# Power_MPU.net
KiCad netlist of a schematic drawn in Altium Designer
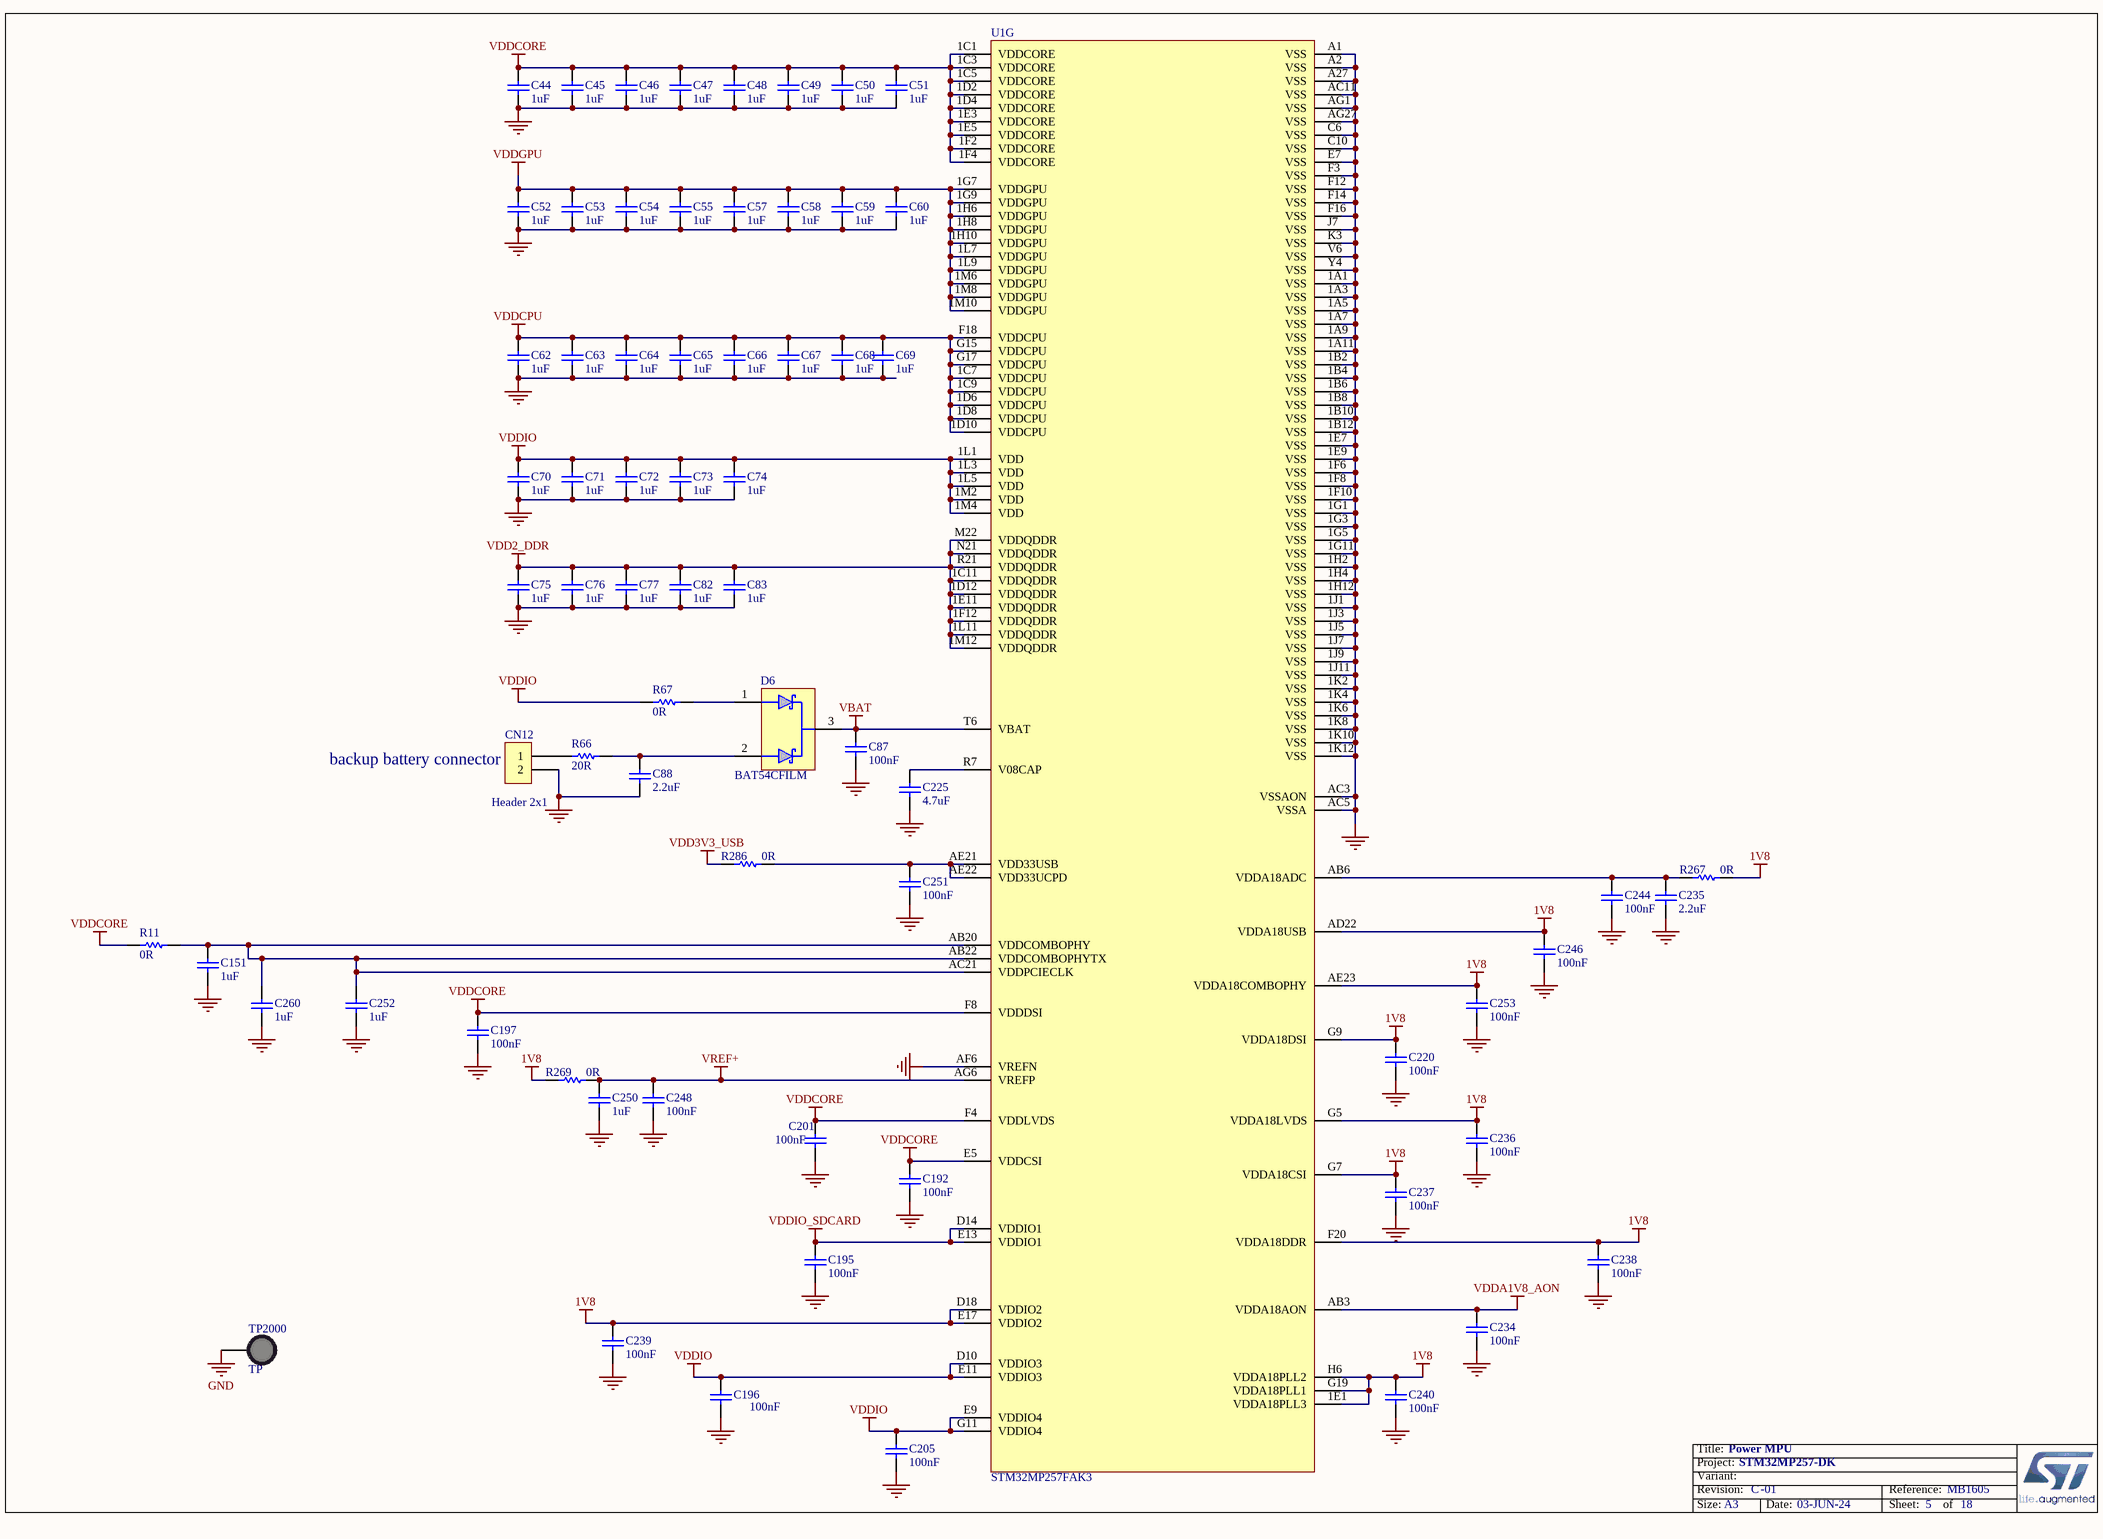
[diagram p0: Power_MPU.SchDoc]

(export (version "E")
  (design (tool "Eeschema 10.0.6"))
  (components
    (comp (ref "C44")
      (value "1uF")
      (footprint "C0201_MURATA_GRM033_H0P3")
      (description "Capacitor, MLCC, 1uF, 6.3V, X5R, +/-20%, 0201, T=0,3mm")
      (fields (field (name "INTERNAL_PART_NUMBER") "MCD-02377") (field (name "MANUFACTURER") "MURATA"))
      (libsource (lib "MCD_PARTS_database") (part "Capacitor"))
    )
    (comp (ref "C45")
      (value "1uF")
      (footprint "C0201_MURATA_GRM033_H0P3")
      (description "Capacitor, MLCC, 1uF, 6.3V, X5R, +/-20%, 0201, T=0,3mm")
      (fields (field (name "INTERNAL_PART_NUMBER") "MCD-02377") (field (name "MANUFACTURER") "MURATA"))
      (libsource (lib "MCD_PARTS_database") (part "Capacitor"))
    )
    (comp (ref "C46")
      (value "1uF")
      (footprint "C0201_MURATA_GRM033_H0P3")
      (description "Capacitor, MLCC, 1uF, 6.3V, X5R, +/-20%, 0201, T=0,3mm")
      (fields (field (name "INTERNAL_PART_NUMBER") "MCD-02377") (field (name "MANUFACTURER") "MURATA"))
      (libsource (lib "MCD_PARTS_database") (part "Capacitor"))
    )
    (comp (ref "C47")
      (value "1uF")
      (footprint "C0201_MURATA_GRM033_H0P3")
      (description "Capacitor, MLCC, 1uF, 6.3V, X5R, +/-20%, 0201, T=0,3mm")
      (fields (field (name "INTERNAL_PART_NUMBER") "MCD-02377") (field (name "MANUFACTURER") "MURATA"))
      (libsource (lib "MCD_PARTS_database") (part "Capacitor"))
    )
    (comp (ref "C48")
      (value "1uF")
      (footprint "C0201_MURATA_GRM033_H0P3")
      (description "Capacitor, MLCC, 1uF, 6.3V, X5R, +/-20%, 0201, T=0,3mm")
      (fields (field (name "INTERNAL_PART_NUMBER") "MCD-02377") (field (name "MANUFACTURER") "MURATA"))
      (libsource (lib "MCD_PARTS_database") (part "Capacitor"))
    )
    (comp (ref "C49")
      (value "1uF")
      (footprint "C0201_MURATA_GRM033_H0P3")
      (description "Capacitor, MLCC, 1uF, 6.3V, X5R, +/-20%, 0201, T=0,3mm")
      (fields (field (name "INTERNAL_PART_NUMBER") "MCD-02377") (field (name "MANUFACTURER") "MURATA"))
      (libsource (lib "MCD_PARTS_database") (part "Capacitor"))
    )
    (comp (ref "C50")
      (value "1uF")
      (footprint "C0201_MURATA_GRM033_H0P3")
      (description "Capacitor, MLCC, 1uF, 6.3V, X5R, +/-20%, 0201, T=0,3mm")
      (fields (field (name "INTERNAL_PART_NUMBER") "MCD-02377") (field (name "MANUFACTURER") "MURATA"))
      (libsource (lib "MCD_PARTS_database") (part "Capacitor"))
    )
    (comp (ref "C51")
      (value "1uF")
      (footprint "C0201_MURATA_GRM033_H0P3")
      (description "Capacitor, MLCC, 1uF, 6.3V, X5R, +/-20%, 0201, T=0,3mm")
      (fields (field (name "INTERNAL_PART_NUMBER") "MCD-02377") (field (name "MANUFACTURER") "MURATA"))
      (libsource (lib "MCD_PARTS_database") (part "Capacitor"))
    )
    (comp (ref "C52")
      (value "1uF")
      (footprint "C0201_MURATA_GRM033_H0P3")
      (description "Capacitor, MLCC, 1uF, 6.3V, X5R, +/-20%, 0201, T=0,3mm")
      (fields (field (name "INTERNAL_PART_NUMBER") "MCD-02377") (field (name "MANUFACTURER") "MURATA"))
      (libsource (lib "MCD_PARTS_database") (part "Capacitor"))
    )
    (comp (ref "C53")
      (value "1uF")
      (footprint "C0201_MURATA_GRM033_H0P3")
      (description "Capacitor, MLCC, 1uF, 6.3V, X5R, +/-20%, 0201, T=0,3mm")
      (fields (field (name "INTERNAL_PART_NUMBER") "MCD-02377") (field (name "MANUFACTURER") "MURATA"))
      (libsource (lib "MCD_PARTS_database") (part "Capacitor"))
    )
    (comp (ref "C54")
      (value "1uF")
      (footprint "C0201_MURATA_GRM033_H0P3")
      (description "Capacitor, MLCC, 1uF, 6.3V, X5R, +/-20%, 0201, T=0,3mm")
      (fields (field (name "INTERNAL_PART_NUMBER") "MCD-02377") (field (name "MANUFACTURER") "MURATA"))
      (libsource (lib "MCD_PARTS_database") (part "Capacitor"))
    )
    (comp (ref "C55")
      (value "1uF")
      (footprint "C0201_MURATA_GRM033_H0P3")
      (description "Capacitor, MLCC, 1uF, 6.3V, X5R, +/-20%, 0201, T=0,3mm")
      (fields (field (name "INTERNAL_PART_NUMBER") "MCD-02377") (field (name "MANUFACTURER") "MURATA"))
      (libsource (lib "MCD_PARTS_database") (part "Capacitor"))
    )
    (comp (ref "C57")
      (value "1uF")
      (footprint "C0201_MURATA_GRM033_H0P3")
      (description "Capacitor, MLCC, 1uF, 6.3V, X5R, +/-20%, 0201, T=0,3mm")
      (fields (field (name "INTERNAL_PART_NUMBER") "MCD-02377") (field (name "MANUFACTURER") "MURATA"))
      (libsource (lib "MCD_PARTS_database") (part "Capacitor"))
    )
    (comp (ref "C58")
      (value "1uF")
      (footprint "C0201_MURATA_GRM033_H0P3")
      (description "Capacitor, MLCC, 1uF, 6.3V, X5R, +/-20%, 0201, T=0,3mm")
      (fields (field (name "INTERNAL_PART_NUMBER") "MCD-02377") (field (name "MANUFACTURER") "MURATA"))
      (libsource (lib "MCD_PARTS_database") (part "Capacitor"))
    )
    (comp (ref "C59")
      (value "1uF")
      (footprint "C0201_MURATA_GRM033_H0P3")
      (description "Capacitor, MLCC, 1uF, 6.3V, X5R, +/-20%, 0201, T=0,3mm")
      (fields (field (name "INTERNAL_PART_NUMBER") "MCD-02377") (field (name "MANUFACTURER") "MURATA"))
      (libsource (lib "MCD_PARTS_database") (part "Capacitor"))
    )
    (comp (ref "C60")
      (value "1uF")
      (footprint "C0201_MURATA_GRM033_H0P3")
      (description "Capacitor, MLCC, 1uF, 6.3V, X5R, +/-20%, 0201, T=0,3mm")
      (fields (field (name "INTERNAL_PART_NUMBER") "MCD-02377") (field (name "MANUFACTURER") "MURATA"))
      (libsource (lib "MCD_PARTS_database") (part "Capacitor"))
    )
    (comp (ref "C62")
      (value "1uF")
      (footprint "C0201_MURATA_GRM033_H0P3")
      (description "Capacitor, MLCC, 1uF, 6.3V, X5R, +/-20%, 0201, T=0,3mm")
      (fields (field (name "INTERNAL_PART_NUMBER") "MCD-02377") (field (name "MANUFACTURER") "MURATA"))
      (libsource (lib "MCD_PARTS_database") (part "Capacitor"))
    )
    (comp (ref "C63")
      (value "1uF")
      (footprint "C0201_MURATA_GRM033_H0P3")
      (description "Capacitor, MLCC, 1uF, 6.3V, X5R, +/-20%, 0201, T=0,3mm")
      (fields (field (name "INTERNAL_PART_NUMBER") "MCD-02377") (field (name "MANUFACTURER") "MURATA"))
      (libsource (lib "MCD_PARTS_database") (part "Capacitor"))
    )
    (comp (ref "C64")
      (value "1uF")
      (footprint "C0201_MURATA_GRM033_H0P3")
      (description "Capacitor, MLCC, 1uF, 6.3V, X5R, +/-20%, 0201, T=0,3mm")
      (fields (field (name "INTERNAL_PART_NUMBER") "MCD-02377") (field (name "MANUFACTURER") "MURATA"))
      (libsource (lib "MCD_PARTS_database") (part "Capacitor"))
    )
    (comp (ref "C65")
      (value "1uF")
      (footprint "C0201_MURATA_GRM033_H0P3")
      (description "Capacitor, MLCC, 1uF, 6.3V, X5R, +/-20%, 0201, T=0,3mm")
      (fields (field (name "INTERNAL_PART_NUMBER") "MCD-02377") (field (name "MANUFACTURER") "MURATA"))
      (libsource (lib "MCD_PARTS_database") (part "Capacitor"))
    )
    (comp (ref "C66")
      (value "1uF")
      (footprint "C0201_MURATA_GRM033_H0P3")
      (description "Capacitor, MLCC, 1uF, 6.3V, X5R, +/-20%, 0201, T=0,3mm")
      (fields (field (name "INTERNAL_PART_NUMBER") "MCD-02377") (field (name "MANUFACTURER") "MURATA"))
      (libsource (lib "MCD_PARTS_database") (part "Capacitor"))
    )
    (comp (ref "C67")
      (value "1uF")
      (footprint "C0201_MURATA_GRM033_H0P3")
      (description "Capacitor, MLCC, 1uF, 6.3V, X5R, +/-20%, 0201, T=0,3mm")
      (fields (field (name "INTERNAL_PART_NUMBER") "MCD-02377") (field (name "MANUFACTURER") "MURATA"))
      (libsource (lib "MCD_PARTS_database") (part "Capacitor"))
    )
    (comp (ref "C68")
      (value "1uF")
      (footprint "C0201_MURATA_GRM033_H0P3")
      (description "Capacitor, MLCC, 1uF, 6.3V, X5R, +/-20%, 0201, T=0,3mm")
      (fields (field (name "INTERNAL_PART_NUMBER") "MCD-02377") (field (name "MANUFACTURER") "MURATA"))
      (libsource (lib "MCD_PARTS_database") (part "Capacitor"))
    )
    (comp (ref "C69")
      (value "1uF")
      (footprint "C0201_MURATA_GRM033_H0P3")
      (description "Capacitor, MLCC, 1uF, 6.3V, X5R, +/-20%, 0201, T=0,3mm")
      (fields (field (name "INTERNAL_PART_NUMBER") "MCD-02377") (field (name "MANUFACTURER") "MURATA"))
      (libsource (lib "MCD_PARTS_database") (part "Capacitor"))
    )
    (comp (ref "C70")
      (value "1uF")
      (footprint "C0201_MURATA_GRM033_H0P3")
      (description "Capacitor, MLCC, 1uF, 6.3V, X5R, +/-20%, 0201, T=0,3mm")
      (fields (field (name "INTERNAL_PART_NUMBER") "MCD-02377") (field (name "MANUFACTURER") "MURATA"))
      (libsource (lib "MCD_PARTS_database") (part "Capacitor"))
    )
    (comp (ref "C71")
      (value "1uF")
      (footprint "C0201_MURATA_GRM033_H0P3")
      (description "Capacitor, MLCC, 1uF, 6.3V, X5R, +/-20%, 0201, T=0,3mm")
      (fields (field (name "INTERNAL_PART_NUMBER") "MCD-02377") (field (name "MANUFACTURER") "MURATA"))
      (libsource (lib "MCD_PARTS_database") (part "Capacitor"))
    )
    (comp (ref "C72")
      (value "1uF")
      (footprint "C0201_MURATA_GRM033_H0P3")
      (description "Capacitor, MLCC, 1uF, 6.3V, X5R, +/-20%, 0201, T=0,3mm")
      (fields (field (name "INTERNAL_PART_NUMBER") "MCD-02377") (field (name "MANUFACTURER") "MURATA"))
      (libsource (lib "MCD_PARTS_database") (part "Capacitor"))
    )
    (comp (ref "C73")
      (value "1uF")
      (footprint "C0201_MURATA_GRM033_H0P3")
      (description "Capacitor, MLCC, 1uF, 6.3V, X5R, +/-20%, 0201, T=0,3mm")
      (fields (field (name "INTERNAL_PART_NUMBER") "MCD-02377") (field (name "MANUFACTURER") "MURATA"))
      (libsource (lib "MCD_PARTS_database") (part "Capacitor"))
    )
    (comp (ref "C74")
      (value "1uF")
      (footprint "C0201_MURATA_GRM033_H0P3")
      (description "Capacitor, MLCC, 1uF, 6.3V, X5R, +/-20%, 0201, T=0,3mm")
      (fields (field (name "INTERNAL_PART_NUMBER") "MCD-02377") (field (name "MANUFACTURER") "MURATA"))
      (libsource (lib "MCD_PARTS_database") (part "Capacitor"))
    )
    (comp (ref "C75")
      (value "1uF")
      (footprint "C0201_MURATA_GRM033_H0P3")
      (description "Capacitor, MLCC, 1uF, 6.3V, X5R, +/-20%, 0201, T=0,3mm")
      (fields (field (name "INTERNAL_PART_NUMBER") "MCD-02377") (field (name "MANUFACTURER") "MURATA"))
      (libsource (lib "MCD_PARTS_database") (part "Capacitor"))
    )
    (comp (ref "C76")
      (value "1uF")
      (footprint "C0201_MURATA_GRM033_H0P3")
      (description "Capacitor, MLCC, 1uF, 6.3V, X5R, +/-20%, 0201, T=0,3mm")
      (fields (field (name "INTERNAL_PART_NUMBER") "MCD-02377") (field (name "MANUFACTURER") "MURATA"))
      (libsource (lib "MCD_PARTS_database") (part "Capacitor"))
    )
    (comp (ref "C77")
      (value "1uF")
      (footprint "C0201_MURATA_GRM033_H0P3")
      (description "Capacitor, MLCC, 1uF, 6.3V, X5R, +/-20%, 0201, T=0,3mm")
      (fields (field (name "INTERNAL_PART_NUMBER") "MCD-02377") (field (name "MANUFACTURER") "MURATA"))
      (libsource (lib "MCD_PARTS_database") (part "Capacitor"))
    )
    (comp (ref "C82")
      (value "1uF")
      (footprint "C0201_MURATA_GRM033_H0P3")
      (description "Capacitor, MLCC, 1uF, 6.3V, X5R, +/-20%, 0201, T=0,3mm")
      (fields (field (name "INTERNAL_PART_NUMBER") "MCD-02377") (field (name "MANUFACTURER") "MURATA"))
      (libsource (lib "MCD_PARTS_database") (part "Capacitor"))
    )
    (comp (ref "C83")
      (value "1uF")
      (footprint "C0201_MURATA_GRM033_H0P3")
      (description "Capacitor, MLCC, 1uF, 6.3V, X5R, +/-20%, 0201, T=0,3mm")
      (fields (field (name "INTERNAL_PART_NUMBER") "MCD-02377") (field (name "MANUFACTURER") "MURATA"))
      (libsource (lib "MCD_PARTS_database") (part "Capacitor"))
    )
    (comp (ref "C87")
      (value "100nF")
      (footprint "C0402")
      (description "Capacitor,100nF,16V,X7R,10%,0402")
      (fields
        (field (name "INTERNAL_PART_NUMBER") "MCD-00006")
        (field (name "MANUFACTURER_PART_NUMBER") "CC0402KRX7R7BB104")
        (field (name "PROVIDED_BY") "SUBCO")
      )
      (libsource (lib "MCD_PARTS_database") (part "Capacitor"))
    )
    (comp (ref "C88")
      (value "2.2uF")
      (footprint "C0402")
      (description "Capacitor, MLCC, 2.2uF, 6V3, X5R,+/-10%, 0402, T=0.5mm")
      (fields (field (name "INTERNAL_PART_NUMBER") "MCD-01823") (field (name "MANUFACTURER") "MURATA"))
      (libsource (lib "MCD_PARTS_database") (part "Capacitor"))
    )
    (comp (ref "C151")
      (value "1uF")
      (footprint "C0201_MURATA_GRM033_H0P3")
      (description "Capacitor, MLCC, 1uF, 6.3V, X5R, +/-20%, 0201, T=0,3mm")
      (fields
        (field (name "INTERNAL_PART_NUMBER") "MCD-02377")
        (field (name "MANUFACTURER_PART_NUMBER") "GRM033R60J105MEA2")
      )
      (libsource (lib "MCD_PARTS_database") (part "Capacitor"))
    )
    (comp (ref "C192")
      (value "100nF")
      (footprint "C0201_MURATA_GRM033_H0P3")
      (description "Capacitor, MLCC,100nF, 10V, X7R, +/-10%, 0201, T=0.3mm")
      (fields (field (name "INTERNAL_PART_NUMBER") "MCD-01535") (field (name "MANUFACTURER") "MURATA"))
      (libsource (lib "MCD_PARTS_database") (part "Capacitor"))
    )
    (comp (ref "C195")
      (value "100nF")
      (footprint "C0201_MURATA_GRM033_H0P3")
      (description "Capacitor, MLCC,100nF, 10V, X7R, +/-10%, 0201, T=0.3mm")
      (fields (field (name "INTERNAL_PART_NUMBER") "MCD-01535") (field (name "MANUFACTURER") "MURATA"))
      (libsource (lib "MCD_PARTS_database") (part "Capacitor"))
    )
    (comp (ref "C196")
      (value "100nF")
      (footprint "C0201_MURATA_GRM033_H0P3")
      (description "Capacitor, MLCC,100nF, 10V, X7R, +/-10%, 0201, T=0.3mm")
      (fields (field (name "INTERNAL_PART_NUMBER") "MCD-01535") (field (name "MANUFACTURER") "MURATA"))
      (libsource (lib "MCD_PARTS_database") (part "Capacitor"))
    )
    (comp (ref "C197")
      (value "100nF")
      (footprint "C0201_MURATA_GRM033_H0P3")
      (description "Capacitor, MLCC,100nF, 10V, X7R, +/-10%, 0201, T=0.3mm")
      (fields (field (name "INTERNAL_PART_NUMBER") "MCD-01535") (field (name "MANUFACTURER") "MURATA"))
      (libsource (lib "MCD_PARTS_database") (part "Capacitor"))
    )
    (comp (ref "C201")
      (value "100nF")
      (footprint "C0201_MURATA_GRM033_H0P3")
      (description "Capacitor, MLCC,100nF, 10V, X7R, +/-10%, 0201, T=0.3mm")
      (fields (field (name "INTERNAL_PART_NUMBER") "MCD-01535") (field (name "MANUFACTURER") "MURATA"))
      (libsource (lib "MCD_PARTS_database") (part "Capacitor"))
    )
    (comp (ref "C205")
      (value "100nF")
      (footprint "C0201_MURATA_GRM033_H0P3")
      (description "Capacitor, MLCC,100nF, 10V, X7R, +/-10%, 0201, T=0.3mm")
      (fields (field (name "INTERNAL_PART_NUMBER") "MCD-01535") (field (name "MANUFACTURER") "MURATA"))
      (libsource (lib "MCD_PARTS_database") (part "Capacitor"))
    )
    (comp (ref "C220")
      (value "100nF")
      (footprint "C0201_MURATA_GRM033_H0P3")
      (description "Capacitor, MLCC,100nF, 10V, X7R, +/-10%, 0201, T=0.3mm")
      (fields (field (name "INTERNAL_PART_NUMBER") "MCD-01535") (field (name "MANUFACTURER") "MURATA"))
      (libsource (lib "MCD_PARTS_database") (part "Capacitor"))
    )
    (comp (ref "C225")
      (value "4.7uF")
      (footprint "C0201_H0P5")
      (description "Capacitor, MLCC, 4,7uF, 6V3, X5R, +/-20%, 0201, T=0.5mm")
      (fields (field (name "INTERNAL_PART_NUMBER") "MCD-01534") (field (name "MANUFACTURER") "MURATA"))
      (libsource (lib "MCD_PARTS_database") (part "Capacitor"))
    )
    (comp (ref "C234")
      (value "100nF")
      (footprint "C0201_MURATA_GRM033_H0P3")
      (description "Capacitor, MLCC,100nF, 10V, X7R, +/-10%, 0201, T=0.3mm")
      (fields (field (name "INTERNAL_PART_NUMBER") "MCD-01535") (field (name "MANUFACTURER") "MURATA"))
      (libsource (lib "MCD_PARTS_database") (part "Capacitor"))
    )
    (comp (ref "C235")
      (value "2.2uF")
      (footprint "C0201_H0P5")
      (description "Capacitor, MLCC, 2.2uF, 10V, X5R,+/-10%, 0201, T=0.5mm")
      (fields (field (name "INTERNAL_PART_NUMBER") "MCD-02235") (field (name "MANUFACTURER") "MURATA"))
      (libsource (lib "MCD_PARTS_database") (part "Capacitor"))
    )
    (comp (ref "C236")
      (value "100nF")
      (footprint "C0201_MURATA_GRM033_H0P3")
      (description "Capacitor, MLCC,100nF, 10V, X7R, +/-10%, 0201, T=0.3mm")
      (fields (field (name "INTERNAL_PART_NUMBER") "MCD-01535") (field (name "MANUFACTURER") "MURATA"))
      (libsource (lib "MCD_PARTS_database") (part "Capacitor"))
    )
    (comp (ref "C237")
      (value "100nF")
      (footprint "C0201_MURATA_GRM033_H0P3")
      (description "Capacitor, MLCC,100nF, 10V, X7R, +/-10%, 0201, T=0.3mm")
      (fields (field (name "INTERNAL_PART_NUMBER") "MCD-01535") (field (name "MANUFACTURER") "MURATA"))
      (libsource (lib "MCD_PARTS_database") (part "Capacitor"))
    )
    (comp (ref "C238")
      (value "100nF")
      (footprint "C0201_MURATA_GRM033_H0P3")
      (description "Capacitor, MLCC,100nF, 10V, X7R, +/-10%, 0201, T=0.3mm")
      (fields (field (name "INTERNAL_PART_NUMBER") "MCD-01535") (field (name "MANUFACTURER") "MURATA"))
      (libsource (lib "MCD_PARTS_database") (part "Capacitor"))
    )
    (comp (ref "C239")
      (value "100nF")
      (footprint "C0201_MURATA_GRM033_H0P3")
      (description "Capacitor, MLCC,100nF, 10V, X7R, +/-10%, 0201, T=0.3mm")
      (fields (field (name "INTERNAL_PART_NUMBER") "MCD-01535") (field (name "MANUFACTURER") "MURATA"))
      (libsource (lib "MCD_PARTS_database") (part "Capacitor"))
    )
    (comp (ref "C240")
      (value "100nF")
      (footprint "C0201_MURATA_GRM033_H0P3")
      (description "Capacitor, MLCC,100nF, 10V, X7R, +/-10%, 0201, T=0.3mm")
      (fields (field (name "INTERNAL_PART_NUMBER") "MCD-01535") (field (name "MANUFACTURER") "MURATA"))
      (libsource (lib "MCD_PARTS_database") (part "Capacitor"))
    )
    (comp (ref "C244")
      (value "100nF")
      (footprint "C0201_MURATA_GRM033_H0P3")
      (description "Capacitor, MLCC,100nF, 10V, X7R, +/-10%, 0201, T=0.3mm")
      (fields (field (name "INTERNAL_PART_NUMBER") "MCD-01535") (field (name "MANUFACTURER") "MURATA"))
      (libsource (lib "MCD_PARTS_database") (part "Capacitor"))
    )
    (comp (ref "C246")
      (value "100nF")
      (footprint "C0201_MURATA_GRM033_H0P3")
      (description "Capacitor, MLCC,100nF, 10V, X7R, +/-10%, 0201, T=0.3mm")
      (fields (field (name "INTERNAL_PART_NUMBER") "MCD-01535") (field (name "MANUFACTURER") "MURATA"))
      (libsource (lib "MCD_PARTS_database") (part "Capacitor"))
    )
    (comp (ref "C248")
      (value "100nF")
      (footprint "C0201_MURATA_GRM033_H0P3")
      (description "Capacitor, MLCC,100nF, 10V, X7R, +/-10%, 0201, T=0.3mm")
      (fields (field (name "INTERNAL_PART_NUMBER") "MCD-01535") (field (name "MANUFACTURER") "MURATA"))
      (libsource (lib "MCD_PARTS_database") (part "Capacitor"))
    )
    (comp (ref "C250")
      (value "1uF")
      (footprint "C0201_MURATA_GRM033_H0P3")
      (description "Capacitor, MLCC, 1uF, 6.3V, X5R, +/-20%, 0201, T=0,3mm")
      (fields
        (field (name "INTERNAL_PART_NUMBER") "MCD-02377")
        (field (name "MANUFACTURER_PART_NUMBER") "GRM033R60J105MEA2")
      )
      (libsource (lib "MCD_PARTS_database") (part "Capacitor"))
    )
    (comp (ref "C251")
      (value "100nF")
      (footprint "C0201_MURATA_GRM033_H0P3")
      (description "Capacitor, MLCC,100nF, 10V, X7R, +/-10%, 0201, T=0.3mm")
      (fields (field (name "INTERNAL_PART_NUMBER") "MCD-01535") (field (name "MANUFACTURER") "MURATA"))
      (libsource (lib "MCD_PARTS_database") (part "Capacitor"))
    )
    (comp (ref "C252")
      (value "1uF")
      (footprint "C0201_MURATA_GRM033_H0P3")
      (description "Capacitor, MLCC, 1uF, 6.3V, X5R, +/-20%, 0201, T=0,3mm")
      (fields
        (field (name "INTERNAL_PART_NUMBER") "MCD-02377")
        (field (name "MANUFACTURER_PART_NUMBER") "GRM033R60J105MEA2")
      )
      (libsource (lib "MCD_PARTS_database") (part "Capacitor"))
    )
    (comp (ref "C253")
      (value "100nF")
      (footprint "C0201_MURATA_GRM033_H0P3")
      (description "Capacitor, MLCC,100nF, 10V, X7R, +/-10%, 0201, T=0.3mm")
      (fields (field (name "INTERNAL_PART_NUMBER") "MCD-01535") (field (name "MANUFACTURER") "MURATA"))
      (libsource (lib "MCD_PARTS_database") (part "Capacitor"))
    )
    (comp (ref "C260")
      (value "1uF")
      (footprint "C0201_MURATA_GRM033_H0P3")
      (description "Capacitor, MLCC, 1uF, 6.3V, X5R, +/-20%, 0201, T=0,3mm")
      (fields
        (field (name "INTERNAL_PART_NUMBER") "MCD-02377")
        (field (name "MANUFACTURER_PART_NUMBER") "GRM033R60J105MEA2")
      )
      (libsource (lib "MCD_PARTS_database") (part "Capacitor"))
    )
    (comp (ref "CN12")
      (value "Header 2x1")
      (footprint "CON_MOLEX_53047-0210")
      (description "Header 2 circuits, 1.25mm Pitch ,  Vertical, with Friction Lock")
      (fields
        (field (name "INTERNAL_PART_NUMBER") "MCD-00655")
        (field (name "MANUFACTURER_PART_NUMBER") "53047-0210")
        (field (name "PROVIDED_BY") "SUBCO")
      )
      (libsource (lib "MCD_PARTS_database") (part "Header 2x1"))
    )
    (comp (ref "D6")
      (value "BAT54CFILM")
      (footprint "DIO_SOT23")
      (description "Diode, Schottky, Dual Common Cathode, 0V3, 300mA, 40V, SOT-23")
      (fields
        (field (name "INTERNAL_PART_NUMBER") "MCD-03280")
        (field (name "MANUFACTURER") "STMICROELECTRONICS")
      )
      (libsource (lib "MCD_PARTS_database") (part "DIODE_3P_DUAL_COMMON_CATHODE"))
    )
    (comp (ref "R11")
      (value "0R")
      (footprint "R0603")
      (description "Resistor, 0R, 0603, +/-5%, 1/10W")
      (fields (field (name "INTERNAL_PART_NUMBER") "MCD-00056") (field (name "MANUFACTURER") "YAGEO"))
      (libsource (lib "MCD_PARTS_database") (part "Resistor"))
    )
    (comp (ref "R66")
      (value "20R")
      (footprint "R0402")
      (description "Resistor, 20R, 0402, +/-1%, 1/16W")
      (fields (field (name "INTERNAL_PART_NUMBER") "MCD-00058") (field (name "BMS_PART_NUMBER") "9131027"))
      (libsource (lib "MCD_PARTS_database") (part "Resistor"))
    )
    (comp (ref "R67")
      (value "0R")
      (footprint "R0402")
      (description "Resistor, 0R, 0402, +/-5%, 1/16W")
      (fields
        (field (name "INTERNAL_PART_NUMBER") "MCD-00052")
        (field (name "MANUFACTURER_PART_NUMBER") "RC0402JR-070RL")
      )
      (libsource (lib "MCD_PARTS_database") (part "Resistor"))
    )
    (comp (ref "R267")
      (value "0R")
      (footprint "R0402")
      (description "Resistor,0R,0402,5%,1/16W")
      (fields
        (field (name "INTERNAL_PART_NUMBER") "MCD-00052")
        (field (name "MANUFACTURER_PART_NUMBER") "RC0402JR-070RL")
        (field (name "PROVIDED_BY") "SUBCO")
      )
      (libsource (lib "MCD_PARTS_database") (part "Resistor"))
    )
    (comp (ref "R269")
      (value "0R")
      (footprint "R0402")
      (description "Resistor,0R,0402,5%,1/16W")
      (fields
        (field (name "INTERNAL_PART_NUMBER") "MCD-00052")
        (field (name "MANUFACTURER_PART_NUMBER") "RC0402JR-070RL")
        (field (name "PROVIDED_BY") "SUBCO")
      )
      (libsource (lib "MCD_PARTS_database") (part "Resistor"))
    )
    (comp (ref "R286")
      (value "0R")
      (footprint "R0402")
      (description "Resistor,0R,0402,5%,1/16W")
      (fields
        (field (name "INTERNAL_PART_NUMBER") "MCD-00052")
        (field (name "MANUFACTURER_PART_NUMBER") "RC0402JR-070RL")
        (field (name "PROVIDED_BY") "SUBCO")
      )
      (libsource (lib "MCD_PARTS_database") (part "Resistor"))
    )
    (comp (ref "TP2000")
      (value "TP")
      (footprint "TP_PTH-1P02MM_TEST-TERMINAL_RS_101-2391_BLACK")
      (description "Vero Technologies 1.02mm Black Terminal Post")
      (fields
        (field (name "INTERNAL_PART_NUMBER") "MCD-00713")
        (field (name "MANUFACTURER_PART_NUMBER") "20-2137")
        (field (name "PROVIDED_BY") "SUBCO")
      )
      (libsource (lib "MCD_PARTS_database") (part "Test_pin_conn_black"))
    )
    (comp (ref "U1")
      (value "STM32MP257FAK3")
      (footprint "ICC_TFBGA424_14X14_P050_H1P20_CODE-B0A2")
      (description "MPU , 2xCortex-A35@1.5GHz, Cortex-M33@400MHz, TFBGA 14x14, pitch 0.5, 648KB SRAM, With Crypto")
      (fields
        (field (name "INTERNAL_PART_NUMBER") "MCD-03375")
        (field (name "MANUFACTURER") "STMICROELECTRONICS")
      )
      (libsource (lib "MCD_PARTS_database") (part "STM32MP257FAK3"))
    )
  )
  (nets
    (net (code "1") (name "1V8") (class "Default")
      (node (ref "C220") (pin "2") (pinfunction "2_2") (pintype "passive"))
      (node (ref "C236") (pin "2") (pinfunction "2_2") (pintype "passive"))
      (node (ref "C237") (pin "2") (pinfunction "2_2") (pintype "passive"))
      (node (ref "C238") (pin "2") (pinfunction "2_2") (pintype "passive"))
      (node (ref "C239") (pin "2") (pinfunction "2_2") (pintype "passive"))
      (node (ref "C240") (pin "2") (pinfunction "2_2") (pintype "passive"))
      (node (ref "C246") (pin "2") (pinfunction "2_2") (pintype "passive"))
      (node (ref "C253") (pin "2") (pinfunction "2_2") (pintype "passive"))
      (node (ref "R267") (pin "2") (pinfunction "2_2") (pintype "passive"))
      (node (ref "R269") (pin "1") (pinfunction "1_1") (pintype "passive"))
      (node (ref "U1") (pin "1E1") (pinfunction "VDDA18PLL3_1E1") (pintype "passive"))
      (node (ref "U1") (pin "AD22") (pinfunction "VDDA18USB_AD22") (pintype "passive"))
      (node (ref "U1") (pin "AE23") (pinfunction "VDDA18COMBOPHY_AE23") (pintype "passive"))
      (node (ref "U1") (pin "D18") (pinfunction "VDDIO2_D18") (pintype "passive"))
      (node (ref "U1") (pin "E17") (pinfunction "VDDIO2_E17") (pintype "passive"))
      (node (ref "U1") (pin "F20") (pinfunction "VDDA18DDR_F20") (pintype "passive"))
      (node (ref "U1") (pin "G19") (pinfunction "VDDA18PLL1_G19") (pintype "passive"))
      (node (ref "U1") (pin "G5") (pinfunction "VDDA18LVDS_G5") (pintype "passive"))
      (node (ref "U1") (pin "G7") (pinfunction "VDDA18CSI_G7") (pintype "passive"))
      (node (ref "U1") (pin "G9") (pinfunction "VDDA18DSI_G9") (pintype "passive"))
      (node (ref "U1") (pin "H6") (pinfunction "VDDA18PLL2_H6") (pintype "passive"))
    )
    (net (code "2") (name "GND") (class "Default")
      (node (ref "C151") (pin "1") (pinfunction "1_1") (pintype "passive"))
      (node (ref "C192") (pin "1") (pinfunction "1_1") (pintype "passive"))
      (node (ref "C195") (pin "1") (pinfunction "1_1") (pintype "passive"))
      (node (ref "C196") (pin "1") (pinfunction "1_1") (pintype "passive"))
      (node (ref "C197") (pin "1") (pinfunction "1_1") (pintype "passive"))
      (node (ref "C201") (pin "1") (pinfunction "1_1") (pintype "passive"))
      (node (ref "C205") (pin "1") (pinfunction "1_1") (pintype "passive"))
      (node (ref "C220") (pin "1") (pinfunction "1_1") (pintype "passive"))
      (node (ref "C225") (pin "1") (pinfunction "1_1") (pintype "passive"))
      (node (ref "C234") (pin "1") (pinfunction "1_1") (pintype "passive"))
      (node (ref "C235") (pin "1") (pinfunction "1_1") (pintype "passive"))
      (node (ref "C236") (pin "1") (pinfunction "1_1") (pintype "passive"))
      (node (ref "C237") (pin "1") (pinfunction "1_1") (pintype "passive"))
      (node (ref "C238") (pin "1") (pinfunction "1_1") (pintype "passive"))
      (node (ref "C239") (pin "1") (pinfunction "1_1") (pintype "passive"))
      (node (ref "C240") (pin "1") (pinfunction "1_1") (pintype "passive"))
      (node (ref "C244") (pin "1") (pinfunction "1_1") (pintype "passive"))
      (node (ref "C246") (pin "1") (pinfunction "1_1") (pintype "passive"))
      (node (ref "C248") (pin "1") (pinfunction "1_1") (pintype "passive"))
      (node (ref "C250") (pin "1") (pinfunction "1_1") (pintype "passive"))
      (node (ref "C251") (pin "1") (pinfunction "1_1") (pintype "passive"))
      (node (ref "C252") (pin "1") (pinfunction "1_1") (pintype "passive"))
      (node (ref "C253") (pin "1") (pinfunction "1_1") (pintype "passive"))
      (node (ref "C260") (pin "1") (pinfunction "1_1") (pintype "passive"))
      (node (ref "C44") (pin "2") (pinfunction "2_2") (pintype "passive"))
      (node (ref "C45") (pin "1") (pinfunction "1_1") (pintype "passive"))
      (node (ref "C46") (pin "1") (pinfunction "1_1") (pintype "passive"))
      (node (ref "C47") (pin "2") (pinfunction "2_2") (pintype "passive"))
      (node (ref "C48") (pin "1") (pinfunction "1_1") (pintype "passive"))
      (node (ref "C49") (pin "1") (pinfunction "1_1") (pintype "passive"))
      (node (ref "C50") (pin "1") (pinfunction "1_1") (pintype "passive"))
      (node (ref "C51") (pin "1") (pinfunction "1_1") (pintype "passive"))
      (node (ref "C52") (pin "1") (pinfunction "1_1") (pintype "passive"))
      (node (ref "C53") (pin "1") (pinfunction "1_1") (pintype "passive"))
      (node (ref "C54") (pin "1") (pinfunction "1_1") (pintype "passive"))
      (node (ref "C55") (pin "1") (pinfunction "1_1") (pintype "passive"))
      (node (ref "C57") (pin "1") (pinfunction "1_1") (pintype "passive"))
      (node (ref "C58") (pin "1") (pinfunction "1_1") (pintype "passive"))
      (node (ref "C59") (pin "1") (pinfunction "1_1") (pintype "passive"))
      (node (ref "C60") (pin "1") (pinfunction "1_1") (pintype "passive"))
      (node (ref "C62") (pin "2") (pinfunction "2_2") (pintype "passive"))
      (node (ref "C63") (pin "1") (pinfunction "1_1") (pintype "passive"))
      (node (ref "C64") (pin "1") (pinfunction "1_1") (pintype "passive"))
      (node (ref "C65") (pin "2") (pinfunction "2_2") (pintype "passive"))
      (node (ref "C66") (pin "1") (pinfunction "1_1") (pintype "passive"))
      (node (ref "C67") (pin "1") (pinfunction "1_1") (pintype "passive"))
      (node (ref "C68") (pin "1") (pinfunction "1_1") (pintype "passive"))
      (node (ref "C69") (pin "1") (pinfunction "1_1") (pintype "passive"))
      (node (ref "C70") (pin "2") (pinfunction "2_2") (pintype "passive"))
      (node (ref "C71") (pin "1") (pinfunction "1_1") (pintype "passive"))
      (node (ref "C72") (pin "1") (pinfunction "1_1") (pintype "passive"))
      (node (ref "C73") (pin "2") (pinfunction "2_2") (pintype "passive"))
      (node (ref "C74") (pin "1") (pinfunction "1_1") (pintype "passive"))
      (node (ref "C75") (pin "1") (pinfunction "1_1") (pintype "passive"))
      (node (ref "C76") (pin "1") (pinfunction "1_1") (pintype "passive"))
      (node (ref "C77") (pin "2") (pinfunction "2_2") (pintype "passive"))
      (node (ref "C82") (pin "1") (pinfunction "1_1") (pintype "passive"))
      (node (ref "C83") (pin "1") (pinfunction "1_1") (pintype "passive"))
      (node (ref "C87") (pin "1") (pinfunction "1_1") (pintype "passive"))
      (node (ref "C88") (pin "1") (pinfunction "1_1") (pintype "passive"))
      (node (ref "CN12") (pin "2") (pinfunction "2_2") (pintype "passive"))
      (node (ref "TP2000") (pin "1") (pinfunction "1_1") (pintype "passive"))
      (node (ref "U1") (pin "1A1") (pinfunction "VSS_1A1") (pintype "passive"))
      (node (ref "U1") (pin "1A11") (pinfunction "VSS_1A11") (pintype "passive"))
      (node (ref "U1") (pin "1A3") (pinfunction "VSS_1A3") (pintype "passive"))
      (node (ref "U1") (pin "1A5") (pinfunction "VSS_1A5") (pintype "passive"))
      (node (ref "U1") (pin "1A7") (pinfunction "VSS_1A7") (pintype "passive"))
      (node (ref "U1") (pin "1A9") (pinfunction "VSS_1A9") (pintype "passive"))
      (node (ref "U1") (pin "1B10") (pinfunction "VSS_1B10") (pintype "passive"))
      (node (ref "U1") (pin "1B12") (pinfunction "VSS_1B12") (pintype "passive"))
      (node (ref "U1") (pin "1B2") (pinfunction "VSS_1B2") (pintype "passive"))
      (node (ref "U1") (pin "1B4") (pinfunction "VSS_1B4") (pintype "passive"))
      (node (ref "U1") (pin "1B6") (pinfunction "VSS_1B6") (pintype "passive"))
      (node (ref "U1") (pin "1B8") (pinfunction "VSS_1B8") (pintype "passive"))
      (node (ref "U1") (pin "1E7") (pinfunction "VSS_1E7") (pintype "passive"))
      (node (ref "U1") (pin "1E9") (pinfunction "VSS_1E9") (pintype "passive"))
      (node (ref "U1") (pin "1F10") (pinfunction "VSS_1F10") (pintype "passive"))
      (node (ref "U1") (pin "1F6") (pinfunction "VSS_1F6") (pintype "passive"))
      (node (ref "U1") (pin "1F8") (pinfunction "VSS_1F8") (pintype "passive"))
      (node (ref "U1") (pin "1G1") (pinfunction "VSS_1G1") (pintype "passive"))
      (node (ref "U1") (pin "1G11") (pinfunction "VSS_1G11") (pintype "passive"))
      (node (ref "U1") (pin "1G3") (pinfunction "VSS_1G3") (pintype "passive"))
      (node (ref "U1") (pin "1G5") (pinfunction "VSS_1G5") (pintype "passive"))
      (node (ref "U1") (pin "1H12") (pinfunction "VSS_1H12") (pintype "passive"))
      (node (ref "U1") (pin "1H2") (pinfunction "VSS_1H2") (pintype "passive"))
      (node (ref "U1") (pin "1H4") (pinfunction "VSS_1H4") (pintype "passive"))
      (node (ref "U1") (pin "1J1") (pinfunction "VSS_1J1") (pintype "passive"))
      (node (ref "U1") (pin "1J11") (pinfunction "VSS_1J11") (pintype "passive"))
      (node (ref "U1") (pin "1J3") (pinfunction "VSS_1J3") (pintype "passive"))
      (node (ref "U1") (pin "1J5") (pinfunction "VSS_1J5") (pintype "passive"))
      (node (ref "U1") (pin "1J7") (pinfunction "VSS_1J7") (pintype "passive"))
      (node (ref "U1") (pin "1J9") (pinfunction "VSS_1J9") (pintype "passive"))
      (node (ref "U1") (pin "1K10") (pinfunction "VSS_1K10") (pintype "passive"))
      (node (ref "U1") (pin "1K12") (pinfunction "VSS_1K12") (pintype "passive"))
      (node (ref "U1") (pin "1K2") (pinfunction "VSS_1K2") (pintype "passive"))
      (node (ref "U1") (pin "1K4") (pinfunction "VSS_1K4") (pintype "passive"))
      (node (ref "U1") (pin "1K6") (pinfunction "VSS_1K6") (pintype "passive"))
      (node (ref "U1") (pin "1K8") (pinfunction "VSS_1K8") (pintype "passive"))
      (node (ref "U1") (pin "A1") (pinfunction "VSS_A1") (pintype "passive"))
      (node (ref "U1") (pin "A2") (pinfunction "VSS_A2") (pintype "passive"))
      (node (ref "U1") (pin "A27") (pinfunction "VSS_A27") (pintype "passive"))
      (node (ref "U1") (pin "AC11") (pinfunction "VSS_AC11") (pintype "passive"))
      (node (ref "U1") (pin "AC3") (pinfunction "VSSAON_AC3") (pintype "passive"))
      (node (ref "U1") (pin "AC5") (pinfunction "VSSA_AC5") (pintype "passive"))
      (node (ref "U1") (pin "AF6") (pinfunction "VREFN_AF6") (pintype "passive"))
      (node (ref "U1") (pin "AG1") (pinfunction "VSS_AG1") (pintype "passive"))
      (node (ref "U1") (pin "AG27") (pinfunction "VSS_AG27") (pintype "passive"))
      (node (ref "U1") (pin "C10") (pinfunction "VSS_C10") (pintype "passive"))
      (node (ref "U1") (pin "C6") (pinfunction "VSS_C6") (pintype "passive"))
      (node (ref "U1") (pin "E7") (pinfunction "VSS_E7") (pintype "passive"))
      (node (ref "U1") (pin "F12") (pinfunction "VSS_F12") (pintype "passive"))
      (node (ref "U1") (pin "F14") (pinfunction "VSS_F14") (pintype "passive"))
      (node (ref "U1") (pin "F16") (pinfunction "VSS_F16") (pintype "passive"))
      (node (ref "U1") (pin "F3") (pinfunction "VSS_F3") (pintype "passive"))
      (node (ref "U1") (pin "J7") (pinfunction "VSS_J7") (pintype "passive"))
      (node (ref "U1") (pin "K3") (pinfunction "VSS_K3") (pintype "passive"))
      (node (ref "U1") (pin "V6") (pinfunction "VSS_V6") (pintype "passive"))
      (node (ref "U1") (pin "Y4") (pinfunction "VSS_Y4") (pintype "passive"))
    )
    (net (code "3") (name "Net-(C88-Pad2)") (class "Default")
      (node (ref "C88") (pin "2") (pinfunction "2_2") (pintype "passive"))
      (node (ref "D6") (pin "2") (pinfunction "2_2") (pintype "passive"))
      (node (ref "R66") (pin "2") (pinfunction "2_2") (pintype "passive"))
    )
    (net (code "4") (name "Net-(CN12-Pad1)") (class "Default")
      (node (ref "CN12") (pin "1") (pinfunction "1_1") (pintype "passive"))
      (node (ref "R66") (pin "1") (pinfunction "1_1") (pintype "passive"))
    )
    (net (code "5") (name "Net-(D6-Pad1)") (class "Default")
      (node (ref "D6") (pin "1") (pinfunction "1_1") (pintype "passive"))
      (node (ref "R67") (pin "1") (pinfunction "1_1") (pintype "passive"))
    )
    (net (code "6") (name "Net-(U1G-V08CAP)") (class "Default")
      (node (ref "C225") (pin "2") (pinfunction "2_2") (pintype "passive"))
      (node (ref "U1") (pin "R7") (pinfunction "V08CAP_R7") (pintype "passive"))
    )
    (net (code "7") (name "Net-(U1G-VDD33UCPD)") (class "Default")
      (node (ref "C251") (pin "2") (pinfunction "2_2") (pintype "passive"))
      (node (ref "R286") (pin "2") (pinfunction "2_2") (pintype "passive"))
      (node (ref "U1") (pin "AE21") (pinfunction "VDD33USB_AE21") (pintype "passive"))
      (node (ref "U1") (pin "AE22") (pinfunction "VDD33UCPD_AE22") (pintype "passive"))
    )
    (net (code "8") (name "Net-(U1G-VDDA18ADC)") (class "Default")
      (node (ref "C235") (pin "2") (pinfunction "2_2") (pintype "passive"))
      (node (ref "C244") (pin "2") (pinfunction "2_2") (pintype "passive"))
      (node (ref "R267") (pin "1") (pinfunction "1_1") (pintype "passive"))
      (node (ref "U1") (pin "AB6") (pinfunction "VDDA18ADC_AB6") (pintype "passive"))
    )
    (net (code "9") (name "Net-(U1G-VDDCOMBOPHY)") (class "Default")
      (node (ref "C151") (pin "2") (pinfunction "2_2") (pintype "passive"))
      (node (ref "C252") (pin "2") (pinfunction "2_2") (pintype "passive"))
      (node (ref "C260") (pin "2") (pinfunction "2_2") (pintype "passive"))
      (node (ref "R11") (pin "2") (pinfunction "2_2") (pintype "passive"))
      (node (ref "U1") (pin "AB20") (pinfunction "VDDCOMBOPHY_AB20") (pintype "passive"))
      (node (ref "U1") (pin "AB22") (pinfunction "VDDCOMBOPHYTX_AB22") (pintype "passive"))
      (node (ref "U1") (pin "AC21") (pinfunction "VDDPCIECLK_AC21") (pintype "passive"))
    )
    (net (code "10") (name "VBAT") (class "Default")
      (node (ref "C87") (pin "2") (pinfunction "2_2") (pintype "passive"))
      (node (ref "D6") (pin "3") (pinfunction "3_3") (pintype "passive"))
      (node (ref "U1") (pin "T6") (pinfunction "VBAT_T6") (pintype "passive"))
    )
    (net (code "11") (name "VDD2_DDR") (class "Default")
      (node (ref "C75") (pin "2") (pinfunction "2_2") (pintype "passive"))
      (node (ref "C76") (pin "2") (pinfunction "2_2") (pintype "passive"))
      (node (ref "C77") (pin "1") (pinfunction "1_1") (pintype "passive"))
      (node (ref "C82") (pin "2") (pinfunction "2_2") (pintype "passive"))
      (node (ref "C83") (pin "2") (pinfunction "2_2") (pintype "passive"))
      (node (ref "U1") (pin "1C11") (pinfunction "VDDQDDR_1C11") (pintype "passive"))
      (node (ref "U1") (pin "1D12") (pinfunction "VDDQDDR_1D12") (pintype "passive"))
      (node (ref "U1") (pin "1E11") (pinfunction "VDDQDDR_1E11") (pintype "passive"))
      (node (ref "U1") (pin "1F12") (pinfunction "VDDQDDR_1F12") (pintype "passive"))
      (node (ref "U1") (pin "1L11") (pinfunction "VDDQDDR_1L11") (pintype "passive"))
      (node (ref "U1") (pin "1M12") (pinfunction "VDDQDDR_1M12") (pintype "passive"))
      (node (ref "U1") (pin "M22") (pinfunction "VDDQDDR_M22") (pintype "passive"))
      (node (ref "U1") (pin "N21") (pinfunction "VDDQDDR_N21") (pintype "passive"))
      (node (ref "U1") (pin "R21") (pinfunction "VDDQDDR_R21") (pintype "passive"))
    )
    (net (code "12") (name "VDD3V3_USB") (class "Default")
      (node (ref "R286") (pin "1") (pinfunction "1_1") (pintype "passive"))
    )
    (net (code "13") (name "VDDA1V8_AON") (class "Default")
      (node (ref "C234") (pin "2") (pinfunction "2_2") (pintype "passive"))
      (node (ref "U1") (pin "AB3") (pinfunction "VDDA18AON_AB3") (pintype "passive"))
    )
    (net (code "14") (name "VDDCORE") (class "Default")
      (node (ref "C192") (pin "2") (pinfunction "2_2") (pintype "passive"))
      (node (ref "C197") (pin "2") (pinfunction "2_2") (pintype "passive"))
      (node (ref "C201") (pin "2") (pinfunction "2_2") (pintype "passive"))
      (node (ref "C44") (pin "1") (pinfunction "1_1") (pintype "passive"))
      (node (ref "C45") (pin "2") (pinfunction "2_2") (pintype "passive"))
      (node (ref "C46") (pin "2") (pinfunction "2_2") (pintype "passive"))
      (node (ref "C47") (pin "1") (pinfunction "1_1") (pintype "passive"))
      (node (ref "C48") (pin "2") (pinfunction "2_2") (pintype "passive"))
      (node (ref "C49") (pin "2") (pinfunction "2_2") (pintype "passive"))
      (node (ref "C50") (pin "2") (pinfunction "2_2") (pintype "passive"))
      (node (ref "C51") (pin "2") (pinfunction "2_2") (pintype "passive"))
      (node (ref "R11") (pin "1") (pinfunction "1_1") (pintype "passive"))
      (node (ref "U1") (pin "1C1") (pinfunction "VDDCORE_1C1") (pintype "passive"))
      (node (ref "U1") (pin "1C3") (pinfunction "VDDCORE_1C3") (pintype "passive"))
      (node (ref "U1") (pin "1C5") (pinfunction "VDDCORE_1C5") (pintype "passive"))
      (node (ref "U1") (pin "1D2") (pinfunction "VDDCORE_1D2") (pintype "passive"))
      (node (ref "U1") (pin "1D4") (pinfunction "VDDCORE_1D4") (pintype "passive"))
      (node (ref "U1") (pin "1E3") (pinfunction "VDDCORE_1E3") (pintype "passive"))
      (node (ref "U1") (pin "1E5") (pinfunction "VDDCORE_1E5") (pintype "passive"))
      (node (ref "U1") (pin "1F2") (pinfunction "VDDCORE_1F2") (pintype "passive"))
      (node (ref "U1") (pin "1F4") (pinfunction "VDDCORE_1F4") (pintype "passive"))
      (node (ref "U1") (pin "E5") (pinfunction "VDDCSI_E5") (pintype "passive"))
      (node (ref "U1") (pin "F4") (pinfunction "VDDLVDS_F4") (pintype "passive"))
      (node (ref "U1") (pin "F8") (pinfunction "VDDDSI_F8") (pintype "passive"))
    )
    (net (code "15") (name "VDDCPU") (class "Default")
      (node (ref "C62") (pin "1") (pinfunction "1_1") (pintype "passive"))
      (node (ref "C63") (pin "2") (pinfunction "2_2") (pintype "passive"))
      (node (ref "C64") (pin "2") (pinfunction "2_2") (pintype "passive"))
      (node (ref "C65") (pin "1") (pinfunction "1_1") (pintype "passive"))
      (node (ref "C66") (pin "2") (pinfunction "2_2") (pintype "passive"))
      (node (ref "C67") (pin "2") (pinfunction "2_2") (pintype "passive"))
      (node (ref "C68") (pin "2") (pinfunction "2_2") (pintype "passive"))
      (node (ref "C69") (pin "2") (pinfunction "2_2") (pintype "passive"))
      (node (ref "U1") (pin "1C7") (pinfunction "VDDCPU_1C7") (pintype "passive"))
      (node (ref "U1") (pin "1C9") (pinfunction "VDDCPU_1C9") (pintype "passive"))
      (node (ref "U1") (pin "1D10") (pinfunction "VDDCPU_1D10") (pintype "passive"))
      (node (ref "U1") (pin "1D6") (pinfunction "VDDCPU_1D6") (pintype "passive"))
      (node (ref "U1") (pin "1D8") (pinfunction "VDDCPU_1D8") (pintype "passive"))
      (node (ref "U1") (pin "F18") (pinfunction "VDDCPU_F18") (pintype "passive"))
      (node (ref "U1") (pin "G15") (pinfunction "VDDCPU_G15") (pintype "passive"))
      (node (ref "U1") (pin "G17") (pinfunction "VDDCPU_G17") (pintype "passive"))
    )
    (net (code "16") (name "VDDGPU") (class "Default")
      (node (ref "C52") (pin "2") (pinfunction "2_2") (pintype "passive"))
      (node (ref "C53") (pin "2") (pinfunction "2_2") (pintype "passive"))
      (node (ref "C54") (pin "2") (pinfunction "2_2") (pintype "passive"))
      (node (ref "C55") (pin "2") (pinfunction "2_2") (pintype "passive"))
      (node (ref "C57") (pin "2") (pinfunction "2_2") (pintype "passive"))
      (node (ref "C58") (pin "2") (pinfunction "2_2") (pintype "passive"))
      (node (ref "C59") (pin "2") (pinfunction "2_2") (pintype "passive"))
      (node (ref "C60") (pin "2") (pinfunction "2_2") (pintype "passive"))
      (node (ref "U1") (pin "1G7") (pinfunction "VDDGPU_1G7") (pintype "passive"))
      (node (ref "U1") (pin "1G9") (pinfunction "VDDGPU_1G9") (pintype "passive"))
      (node (ref "U1") (pin "1H10") (pinfunction "VDDGPU_1H10") (pintype "passive"))
      (node (ref "U1") (pin "1H6") (pinfunction "VDDGPU_1H6") (pintype "passive"))
      (node (ref "U1") (pin "1H8") (pinfunction "VDDGPU_1H8") (pintype "passive"))
      (node (ref "U1") (pin "1L7") (pinfunction "VDDGPU_1L7") (pintype "passive"))
      (node (ref "U1") (pin "1L9") (pinfunction "VDDGPU_1L9") (pintype "passive"))
      (node (ref "U1") (pin "1M10") (pinfunction "VDDGPU_1M10") (pintype "passive"))
      (node (ref "U1") (pin "1M6") (pinfunction "VDDGPU_1M6") (pintype "passive"))
      (node (ref "U1") (pin "1M8") (pinfunction "VDDGPU_1M8") (pintype "passive"))
    )
    (net (code "17") (name "VDDIO") (class "Default")
      (node (ref "C196") (pin "2") (pinfunction "2_2") (pintype "passive"))
      (node (ref "C205") (pin "2") (pinfunction "2_2") (pintype "passive"))
      (node (ref "C70") (pin "1") (pinfunction "1_1") (pintype "passive"))
      (node (ref "C71") (pin "2") (pinfunction "2_2") (pintype "passive"))
      (node (ref "C72") (pin "2") (pinfunction "2_2") (pintype "passive"))
      (node (ref "C73") (pin "1") (pinfunction "1_1") (pintype "passive"))
      (node (ref "C74") (pin "2") (pinfunction "2_2") (pintype "passive"))
      (node (ref "R67") (pin "2") (pinfunction "2_2") (pintype "passive"))
      (node (ref "U1") (pin "1L1") (pinfunction "VDD_1L1") (pintype "passive"))
      (node (ref "U1") (pin "1L3") (pinfunction "VDD_1L3") (pintype "passive"))
      (node (ref "U1") (pin "1L5") (pinfunction "VDD_1L5") (pintype "passive"))
      (node (ref "U1") (pin "1M2") (pinfunction "VDD_1M2") (pintype "passive"))
      (node (ref "U1") (pin "1M4") (pinfunction "VDD_1M4") (pintype "passive"))
      (node (ref "U1") (pin "D10") (pinfunction "VDDIO3_D10") (pintype "passive"))
      (node (ref "U1") (pin "E11") (pinfunction "VDDIO3_E11") (pintype "passive"))
      (node (ref "U1") (pin "E9") (pinfunction "VDDIO4_E9") (pintype "passive"))
      (node (ref "U1") (pin "G11") (pinfunction "VDDIO4_G11") (pintype "passive"))
    )
    (net (code "18") (name "VDDIO_SDCARD") (class "Default")
      (node (ref "C195") (pin "2") (pinfunction "2_2") (pintype "passive"))
      (node (ref "U1") (pin "D14") (pinfunction "VDDIO1_D14") (pintype "passive"))
      (node (ref "U1") (pin "E13") (pinfunction "VDDIO1_E13") (pintype "passive"))
    )
    (net (code "19") (name "VREF+") (class "Default")
      (node (ref "C248") (pin "2") (pinfunction "2_2") (pintype "passive"))
      (node (ref "C250") (pin "2") (pinfunction "2_2") (pintype "passive"))
      (node (ref "R269") (pin "2") (pinfunction "2_2") (pintype "passive"))
      (node (ref "U1") (pin "AG6") (pinfunction "VREFP_AG6") (pintype "passive"))
    )
  )
)
